# DigitalInterfaces.net
KiCad netlist of a schematic drawn in Altium Designer
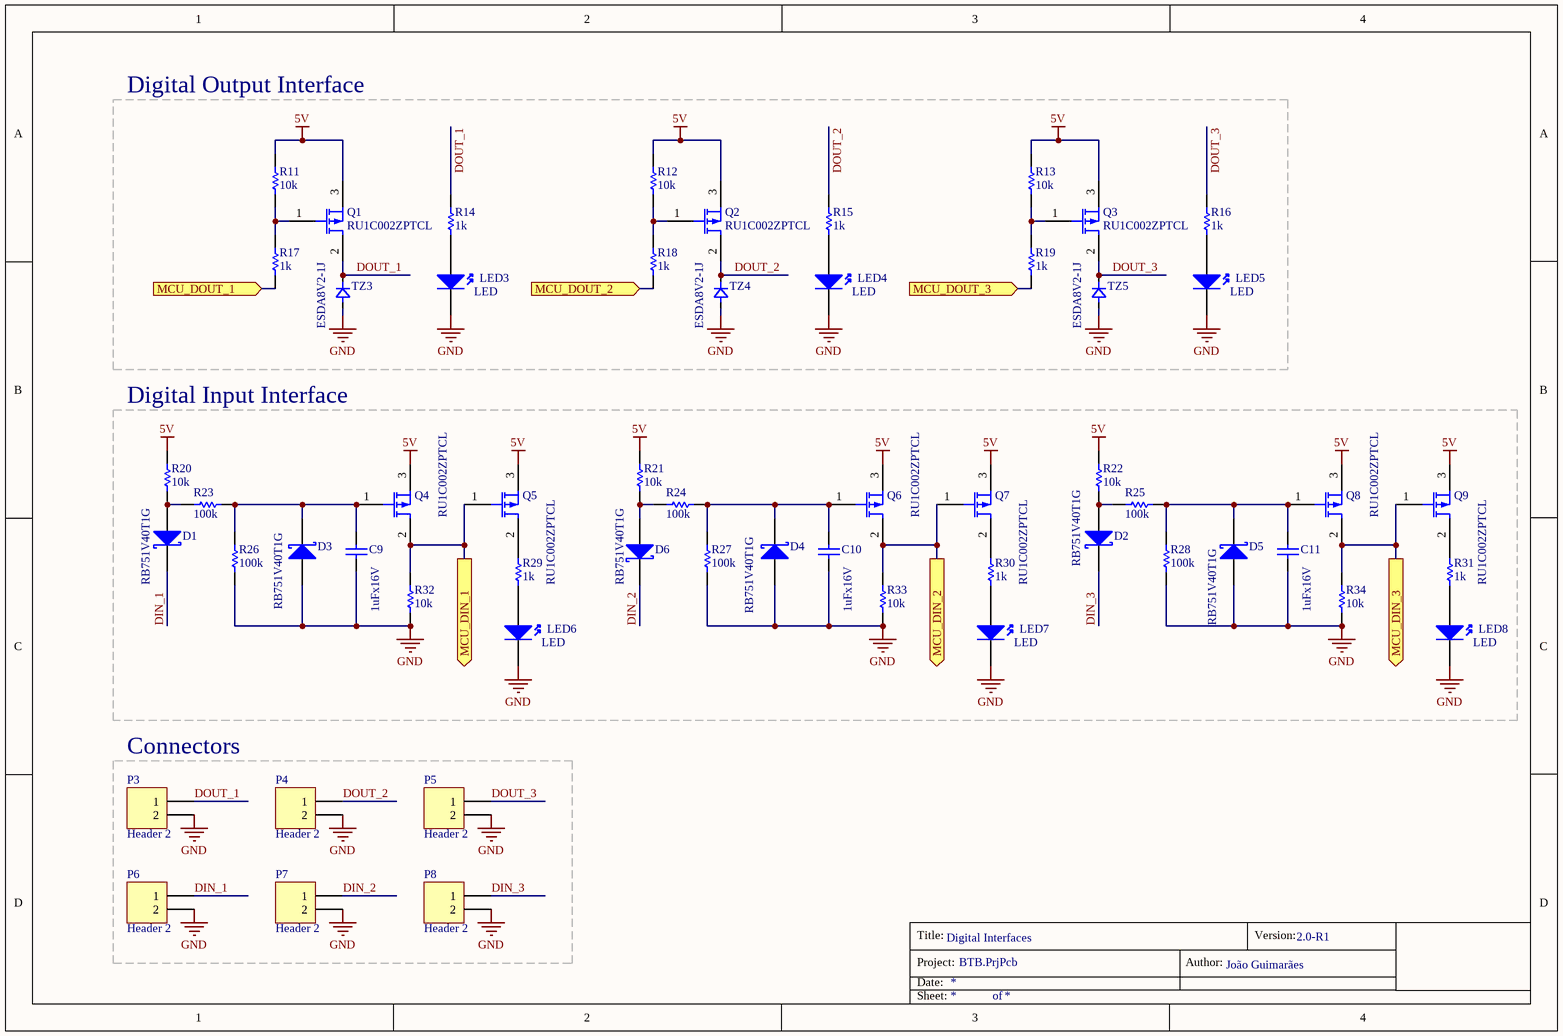
[diagram p0: DigitalInterfaces.SchDoc]

(export (version "E")
  (design (tool "Eeschema 10.0.6"))
  (components
    (comp (ref "C9")
      (value "1uFx16V")
      (footprint "DISC-0805")
      (description "Capacitor")
      (libsource (lib "IntLib") (part "Cap"))
    )
    (comp (ref "C10")
      (value "1uFx16V")
      (footprint "DISC-0805")
      (description "Capacitor")
      (libsource (lib "IntLib") (part "Cap"))
    )
    (comp (ref "C11")
      (value "1uFx16V")
      (footprint "DISC-0805")
      (description "Capacitor")
      (libsource (lib "IntLib") (part "Cap"))
    )
    (comp (ref "D1")
      (value "RB751V40T1G")
      (footprint "DISC-SOD-323")
      (description "Schottky Diode")
      (fields (field (name "PUBLISHER") "Altium Limited"))
      (libsource (lib "IntLib") (part "D Schottky"))
    )
    (comp (ref "D2")
      (value "RB751V40T1G")
      (footprint "DISC-SOD-323")
      (description "Schottky Diode")
      (fields (field (name "PUBLISHER") "Altium Limited"))
      (libsource (lib "IntLib") (part "D Schottky"))
    )
    (comp (ref "D3")
      (value "RB751V40T1G")
      (footprint "DISC-SOD-323")
      (description "Schottky Diode")
      (fields (field (name "PUBLISHER") "Altium Limited"))
      (libsource (lib "IntLib") (part "D Schottky"))
    )
    (comp (ref "D4")
      (value "RB751V40T1G")
      (footprint "DISC-SOD-323")
      (description "Schottky Diode")
      (fields (field (name "PUBLISHER") "Altium Limited"))
      (libsource (lib "IntLib") (part "D Schottky"))
    )
    (comp (ref "D5")
      (value "RB751V40T1G")
      (footprint "DISC-SOD-323")
      (description "Schottky Diode")
      (fields (field (name "PUBLISHER") "Altium Limited"))
      (libsource (lib "IntLib") (part "D Schottky"))
    )
    (comp (ref "D6")
      (value "RB751V40T1G")
      (footprint "DISC-SOD-323")
      (description "Schottky Diode")
      (fields (field (name "PUBLISHER") "Altium Limited"))
      (libsource (lib "IntLib") (part "D Schottky"))
    )
    (comp (ref "LED3") (value "LED") (footprint "DISC-LED-0.1-PTH") (libsource (lib "IntLib") (part "LED")))
    (comp (ref "LED4") (value "LED") (footprint "DISC-LED-0.1-PTH") (libsource (lib "IntLib") (part "LED")))
    (comp (ref "LED5") (value "LED") (footprint "DISC-LED-0.1-PTH") (libsource (lib "IntLib") (part "LED")))
    (comp (ref "LED6") (value "LED") (footprint "DISC-LED-0.1-PTH") (libsource (lib "IntLib") (part "LED")))
    (comp (ref "LED7") (value "LED") (footprint "DISC-LED-0.1-PTH") (libsource (lib "IntLib") (part "LED")))
    (comp (ref "LED8") (value "LED") (footprint "DISC-LED-0.1-PTH") (libsource (lib "IntLib") (part "LED")))
    (comp (ref "P3")
      (value "Header 2")
      (footprint "CON-FLEXWIRE-0.5MM2-1X2")
      (description "Header, 2-Pin")
      (fields (field (name "PUBLISHER") "Altium Limited"))
      (libsource (lib "IntLib") (part "Header 2"))
    )
    (comp (ref "P4")
      (value "Header 2")
      (footprint "CON-FLEXWIRE-0.5MM2-1X2")
      (description "Header, 2-Pin")
      (fields (field (name "PUBLISHER") "Altium Limited"))
      (libsource (lib "IntLib") (part "Header 2"))
    )
    (comp (ref "P5")
      (value "Header 2")
      (footprint "CON-FLEXWIRE-0.5MM2-1X2")
      (description "Header, 2-Pin")
      (fields (field (name "PUBLISHER") "Altium Limited"))
      (libsource (lib "IntLib") (part "Header 2"))
    )
    (comp (ref "P6")
      (value "Header 2")
      (footprint "CON-FLEXWIRE-0.5MM2-1X2")
      (description "Header, 2-Pin")
      (fields (field (name "PUBLISHER") "Altium Limited"))
      (libsource (lib "IntLib") (part "Header 2"))
    )
    (comp (ref "P7")
      (value "Header 2")
      (footprint "CON-FLEXWIRE-0.5MM2-1X2")
      (description "Header, 2-Pin")
      (fields (field (name "PUBLISHER") "Altium Limited"))
      (libsource (lib "IntLib") (part "Header 2"))
    )
    (comp (ref "P8")
      (value "Header 2")
      (footprint "CON-FLEXWIRE-0.5MM2-1X2")
      (description "Header, 2-Pin")
      (fields (field (name "PUBLISHER") "Altium Limited"))
      (libsource (lib "IntLib") (part "Header 2"))
    )
    (comp (ref "Q1")
      (value "RU1C002ZPTCL")
      (footprint "DISC-SOT-23")
      (description "P-Channel MOSFET")
      (libsource (lib "IntLib") (part "Transistor-PMOS"))
    )
    (comp (ref "Q2")
      (value "RU1C002ZPTCL")
      (footprint "DISC-SOT-23")
      (description "P-Channel MOSFET")
      (libsource (lib "IntLib") (part "Transistor-PMOS"))
    )
    (comp (ref "Q3")
      (value "RU1C002ZPTCL")
      (footprint "DISC-SOT-23")
      (description "P-Channel MOSFET")
      (libsource (lib "IntLib") (part "Transistor-PMOS"))
    )
    (comp (ref "Q4")
      (value "RU1C002ZPTCL")
      (footprint "DISC-SOT-23")
      (description "P-Channel MOSFET")
      (libsource (lib "IntLib") (part "Transistor-PMOS"))
    )
    (comp (ref "Q5")
      (value "RU1C002ZPTCL")
      (footprint "DISC-SOT-23")
      (description "P-Channel MOSFET")
      (libsource (lib "IntLib") (part "Transistor-PMOS"))
    )
    (comp (ref "Q6")
      (value "RU1C002ZPTCL")
      (footprint "DISC-SOT-23")
      (description "P-Channel MOSFET")
      (libsource (lib "IntLib") (part "Transistor-PMOS"))
    )
    (comp (ref "Q7")
      (value "RU1C002ZPTCL")
      (footprint "DISC-SOT-23")
      (description "P-Channel MOSFET")
      (libsource (lib "IntLib") (part "Transistor-PMOS"))
    )
    (comp (ref "Q8")
      (value "RU1C002ZPTCL")
      (footprint "DISC-SOT-23")
      (description "P-Channel MOSFET")
      (libsource (lib "IntLib") (part "Transistor-PMOS"))
    )
    (comp (ref "Q9")
      (value "RU1C002ZPTCL")
      (footprint "DISC-SOT-23")
      (description "P-Channel MOSFET")
      (libsource (lib "IntLib") (part "Transistor-PMOS"))
    )
    (comp (ref "R11")
      (value "10k")
      (footprint "DISC-0805")
      (description "Resistor")
      (libsource (lib "IntLib") (part "Res"))
    )
    (comp (ref "R12")
      (value "10k")
      (footprint "DISC-0805")
      (description "Resistor")
      (libsource (lib "IntLib") (part "Res"))
    )
    (comp (ref "R13")
      (value "10k")
      (footprint "DISC-0805")
      (description "Resistor")
      (libsource (lib "IntLib") (part "Res"))
    )
    (comp (ref "R14")
      (value "1k")
      (footprint "DISC-0805")
      (description "Resistor")
      (libsource (lib "IntLib") (part "Res"))
    )
    (comp (ref "R15")
      (value "1k")
      (footprint "DISC-0805")
      (description "Resistor")
      (libsource (lib "IntLib") (part "Res"))
    )
    (comp (ref "R16")
      (value "1k")
      (footprint "DISC-0805")
      (description "Resistor")
      (libsource (lib "IntLib") (part "Res"))
    )
    (comp (ref "R17")
      (value "1k")
      (footprint "DISC-0805")
      (description "Resistor")
      (libsource (lib "IntLib") (part "Res"))
    )
    (comp (ref "R18")
      (value "1k")
      (footprint "DISC-0805")
      (description "Resistor")
      (libsource (lib "IntLib") (part "Res"))
    )
    (comp (ref "R19")
      (value "1k")
      (footprint "DISC-0805")
      (description "Resistor")
      (libsource (lib "IntLib") (part "Res"))
    )
    (comp (ref "R20")
      (value "10k")
      (footprint "DISC-0805")
      (description "Resistor")
      (libsource (lib "IntLib") (part "Res"))
    )
    (comp (ref "R21")
      (value "10k")
      (footprint "DISC-0805")
      (description "Resistor")
      (libsource (lib "IntLib") (part "Res"))
    )
    (comp (ref "R22")
      (value "10k")
      (footprint "DISC-0805")
      (description "Resistor")
      (libsource (lib "IntLib") (part "Res"))
    )
    (comp (ref "R23")
      (value "100k")
      (footprint "DISC-0805")
      (description "Resistor")
      (libsource (lib "IntLib") (part "Res"))
    )
    (comp (ref "R24")
      (value "100k")
      (footprint "DISC-0805")
      (description "Resistor")
      (libsource (lib "IntLib") (part "Res"))
    )
    (comp (ref "R25")
      (value "100k")
      (footprint "DISC-0805")
      (description "Resistor")
      (libsource (lib "IntLib") (part "Res"))
    )
    (comp (ref "R26")
      (value "100k")
      (footprint "DISC-0805")
      (description "Resistor")
      (libsource (lib "IntLib") (part "Res"))
    )
    (comp (ref "R27")
      (value "100k")
      (footprint "DISC-0805")
      (description "Resistor")
      (libsource (lib "IntLib") (part "Res"))
    )
    (comp (ref "R28")
      (value "100k")
      (footprint "DISC-0805")
      (description "Resistor")
      (libsource (lib "IntLib") (part "Res"))
    )
    (comp (ref "R29")
      (value "1k")
      (footprint "DISC-0805")
      (description "Resistor")
      (libsource (lib "IntLib") (part "Res"))
    )
    (comp (ref "R30")
      (value "1k")
      (footprint "DISC-0805")
      (description "Resistor")
      (libsource (lib "IntLib") (part "Res"))
    )
    (comp (ref "R31")
      (value "1k")
      (footprint "DISC-0805")
      (description "Resistor")
      (libsource (lib "IntLib") (part "Res"))
    )
    (comp (ref "R32")
      (value "10k")
      (footprint "DISC-0805")
      (description "Resistor")
      (libsource (lib "IntLib") (part "Res"))
    )
    (comp (ref "R33")
      (value "10k")
      (footprint "DISC-0805")
      (description "Resistor")
      (libsource (lib "IntLib") (part "Res"))
    )
    (comp (ref "R34")
      (value "10k")
      (footprint "DISC-0805")
      (description "Resistor")
      (libsource (lib "IntLib") (part "Res"))
    )
    (comp (ref "TZ3")
      (value "ESDA8V2-1J")
      (footprint "DISC-SOD-323")
      (description "TVZ-Unidirectional")
      (libsource (lib "IntLib") (part "TVZ-Unidirectional"))
    )
    (comp (ref "TZ4")
      (value "ESDA8V2-1J")
      (footprint "DISC-SOD-323")
      (description "TVZ-Unidirectional")
      (libsource (lib "IntLib") (part "TVZ-Unidirectional"))
    )
    (comp (ref "TZ5")
      (value "ESDA8V2-1J")
      (footprint "DISC-SOD-323")
      (description "TVZ-Unidirectional")
      (libsource (lib "IntLib") (part "TVZ-Unidirectional"))
    )
  )
  (nets
    (net (code "1") (name "/DIN_1") (class "Default")
      (node (ref "D1") (pin "2") (pinfunction "K_2") (pintype "passive"))
      (node (ref "P6") (pin "1") (pinfunction "1_1") (pintype "passive"))
    )
    (net (code "2") (name "/DIN_2") (class "Default")
      (node (ref "D6") (pin "2") (pinfunction "K_2") (pintype "passive"))
      (node (ref "P7") (pin "1") (pinfunction "1_1") (pintype "passive"))
    )
    (net (code "3") (name "/DIN_3") (class "Default")
      (node (ref "D2") (pin "2") (pinfunction "K_2") (pintype "passive"))
      (node (ref "P8") (pin "1") (pinfunction "1_1") (pintype "passive"))
    )
    (net (code "4") (name "/DOUT_1") (class "Default")
      (node (ref "P3") (pin "1") (pinfunction "1_1") (pintype "passive"))
      (node (ref "Q1") (pin "2") (pinfunction "D_2") (pintype "passive"))
      (node (ref "R14") (pin "2") (pinfunction "2_2") (pintype "passive"))
      (node (ref "TZ3") (pin "2") (pinfunction "C_2") (pintype "passive"))
    )
    (net (code "5") (name "/DOUT_2") (class "Default")
      (node (ref "P4") (pin "1") (pinfunction "1_1") (pintype "passive"))
      (node (ref "Q2") (pin "2") (pinfunction "D_2") (pintype "passive"))
      (node (ref "R15") (pin "2") (pinfunction "2_2") (pintype "passive"))
      (node (ref "TZ4") (pin "2") (pinfunction "C_2") (pintype "passive"))
    )
    (net (code "6") (name "/DOUT_3") (class "Default")
      (node (ref "P5") (pin "1") (pinfunction "1_1") (pintype "passive"))
      (node (ref "Q3") (pin "2") (pinfunction "D_2") (pintype "passive"))
      (node (ref "R16") (pin "2") (pinfunction "2_2") (pintype "passive"))
      (node (ref "TZ5") (pin "2") (pinfunction "C_2") (pintype "passive"))
    )
    (net (code "7") (name "/MCU_DIN_1") (class "Default")
      (node (ref "Q4") (pin "2") (pinfunction "D_2") (pintype "passive"))
      (node (ref "Q5") (pin "1") (pinfunction "G_1") (pintype "passive"))
      (node (ref "R32") (pin "2") (pinfunction "2_2") (pintype "passive"))
    )
    (net (code "8") (name "/MCU_DIN_2") (class "Default")
      (node (ref "Q6") (pin "2") (pinfunction "D_2") (pintype "passive"))
      (node (ref "Q7") (pin "1") (pinfunction "G_1") (pintype "passive"))
      (node (ref "R33") (pin "2") (pinfunction "2_2") (pintype "passive"))
    )
    (net (code "9") (name "/MCU_DIN_3") (class "Default")
      (node (ref "Q8") (pin "2") (pinfunction "D_2") (pintype "passive"))
      (node (ref "Q9") (pin "1") (pinfunction "G_1") (pintype "passive"))
      (node (ref "R34") (pin "2") (pinfunction "2_2") (pintype "passive"))
    )
    (net (code "10") (name "/MCU_DOUT_1") (class "Default")
      (node (ref "R17") (pin "2") (pinfunction "2_2") (pintype "passive"))
    )
    (net (code "11") (name "/MCU_DOUT_2") (class "Default")
      (node (ref "R18") (pin "2") (pinfunction "2_2") (pintype "passive"))
    )
    (net (code "12") (name "/MCU_DOUT_3") (class "Default")
      (node (ref "R19") (pin "2") (pinfunction "2_2") (pintype "passive"))
    )
    (net (code "13") (name "5V") (class "Default")
      (node (ref "Q1") (pin "3") (pinfunction "S_3") (pintype "passive"))
      (node (ref "Q2") (pin "3") (pinfunction "S_3") (pintype "passive"))
      (node (ref "Q3") (pin "3") (pinfunction "S_3") (pintype "passive"))
      (node (ref "Q4") (pin "3") (pinfunction "S_3") (pintype "passive"))
      (node (ref "Q5") (pin "3") (pinfunction "S_3") (pintype "passive"))
      (node (ref "Q6") (pin "3") (pinfunction "S_3") (pintype "passive"))
      (node (ref "Q7") (pin "3") (pinfunction "S_3") (pintype "passive"))
      (node (ref "Q8") (pin "3") (pinfunction "S_3") (pintype "passive"))
      (node (ref "Q9") (pin "3") (pinfunction "S_3") (pintype "passive"))
      (node (ref "R11") (pin "1") (pinfunction "1_1") (pintype "passive"))
      (node (ref "R12") (pin "1") (pinfunction "1_1") (pintype "passive"))
      (node (ref "R13") (pin "1") (pinfunction "1_1") (pintype "passive"))
      (node (ref "R20") (pin "1") (pinfunction "1_1") (pintype "passive"))
      (node (ref "R21") (pin "1") (pinfunction "1_1") (pintype "passive"))
      (node (ref "R22") (pin "1") (pinfunction "1_1") (pintype "passive"))
    )
    (net (code "14") (name "GND") (class "Default")
      (node (ref "C10") (pin "1") (pinfunction "1_1") (pintype "passive"))
      (node (ref "C11") (pin "1") (pinfunction "1_1") (pintype "passive"))
      (node (ref "C9") (pin "1") (pinfunction "1_1") (pintype "passive"))
      (node (ref "D3") (pin "1") (pinfunction "A_1") (pintype "passive"))
      (node (ref "D4") (pin "1") (pinfunction "A_1") (pintype "passive"))
      (node (ref "D5") (pin "1") (pinfunction "A_1") (pintype "passive"))
      (node (ref "LED3") (pin "2") (pinfunction "K_2") (pintype "passive"))
      (node (ref "LED4") (pin "2") (pinfunction "K_2") (pintype "passive"))
      (node (ref "LED5") (pin "2") (pinfunction "K_2") (pintype "passive"))
      (node (ref "LED6") (pin "2") (pinfunction "K_2") (pintype "passive"))
      (node (ref "LED7") (pin "2") (pinfunction "K_2") (pintype "passive"))
      (node (ref "LED8") (pin "2") (pinfunction "K_2") (pintype "passive"))
      (node (ref "P3") (pin "2") (pinfunction "2_2") (pintype "passive"))
      (node (ref "P4") (pin "2") (pinfunction "2_2") (pintype "passive"))
      (node (ref "P5") (pin "2") (pinfunction "2_2") (pintype "passive"))
      (node (ref "P6") (pin "2") (pinfunction "2_2") (pintype "passive"))
      (node (ref "P7") (pin "2") (pinfunction "2_2") (pintype "passive"))
      (node (ref "P8") (pin "2") (pinfunction "2_2") (pintype "passive"))
      (node (ref "R26") (pin "1") (pinfunction "1_1") (pintype "passive"))
      (node (ref "R27") (pin "1") (pinfunction "1_1") (pintype "passive"))
      (node (ref "R28") (pin "1") (pinfunction "1_1") (pintype "passive"))
      (node (ref "R32") (pin "1") (pinfunction "1_1") (pintype "passive"))
      (node (ref "R33") (pin "1") (pinfunction "1_1") (pintype "passive"))
      (node (ref "R34") (pin "1") (pinfunction "1_1") (pintype "passive"))
      (node (ref "TZ3") (pin "1") (pinfunction "A_1") (pintype "passive"))
      (node (ref "TZ4") (pin "1") (pinfunction "A_1") (pintype "passive"))
      (node (ref "TZ5") (pin "1") (pinfunction "A_1") (pintype "passive"))
    )
    (net (code "15") (name "Net-(D1-A)") (class "Default")
      (node (ref "D1") (pin "1") (pinfunction "A_1") (pintype "passive"))
      (node (ref "R20") (pin "2") (pinfunction "2_2") (pintype "passive"))
      (node (ref "R23") (pin "2") (pinfunction "2_2") (pintype "passive"))
    )
    (net (code "16") (name "Net-(D2-A)") (class "Default")
      (node (ref "D2") (pin "1") (pinfunction "A_1") (pintype "passive"))
      (node (ref "R22") (pin "2") (pinfunction "2_2") (pintype "passive"))
      (node (ref "R25") (pin "1") (pinfunction "1_1") (pintype "passive"))
    )
    (net (code "17") (name "Net-(D3-K)") (class "Default")
      (node (ref "C9") (pin "2") (pinfunction "2_2") (pintype "passive"))
      (node (ref "D3") (pin "2") (pinfunction "K_2") (pintype "passive"))
      (node (ref "Q4") (pin "1") (pinfunction "G_1") (pintype "passive"))
      (node (ref "R23") (pin "1") (pinfunction "1_1") (pintype "passive"))
      (node (ref "R26") (pin "2") (pinfunction "2_2") (pintype "passive"))
    )
    (net (code "18") (name "Net-(D4-K)") (class "Default")
      (node (ref "C10") (pin "2") (pinfunction "2_2") (pintype "passive"))
      (node (ref "D4") (pin "2") (pinfunction "K_2") (pintype "passive"))
      (node (ref "Q6") (pin "1") (pinfunction "G_1") (pintype "passive"))
      (node (ref "R24") (pin "2") (pinfunction "2_2") (pintype "passive"))
      (node (ref "R27") (pin "2") (pinfunction "2_2") (pintype "passive"))
    )
    (net (code "19") (name "Net-(D5-K)") (class "Default")
      (node (ref "C11") (pin "2") (pinfunction "2_2") (pintype "passive"))
      (node (ref "D5") (pin "2") (pinfunction "K_2") (pintype "passive"))
      (node (ref "Q8") (pin "1") (pinfunction "G_1") (pintype "passive"))
      (node (ref "R25") (pin "2") (pinfunction "2_2") (pintype "passive"))
      (node (ref "R28") (pin "2") (pinfunction "2_2") (pintype "passive"))
    )
    (net (code "20") (name "Net-(D6-A)") (class "Default")
      (node (ref "D6") (pin "1") (pinfunction "A_1") (pintype "passive"))
      (node (ref "R21") (pin "2") (pinfunction "2_2") (pintype "passive"))
      (node (ref "R24") (pin "1") (pinfunction "1_1") (pintype "passive"))
    )
    (net (code "21") (name "Net-(LED3-A)") (class "Default")
      (node (ref "LED3") (pin "1") (pinfunction "A_1") (pintype "passive"))
      (node (ref "R14") (pin "1") (pinfunction "1_1") (pintype "passive"))
    )
    (net (code "22") (name "Net-(LED4-A)") (class "Default")
      (node (ref "LED4") (pin "1") (pinfunction "A_1") (pintype "passive"))
      (node (ref "R15") (pin "1") (pinfunction "1_1") (pintype "passive"))
    )
    (net (code "23") (name "Net-(LED5-A)") (class "Default")
      (node (ref "LED5") (pin "1") (pinfunction "A_1") (pintype "passive"))
      (node (ref "R16") (pin "1") (pinfunction "1_1") (pintype "passive"))
    )
    (net (code "24") (name "Net-(LED6-A)") (class "Default")
      (node (ref "LED6") (pin "1") (pinfunction "A_1") (pintype "passive"))
      (node (ref "R29") (pin "1") (pinfunction "1_1") (pintype "passive"))
    )
    (net (code "25") (name "Net-(LED7-A)") (class "Default")
      (node (ref "LED7") (pin "1") (pinfunction "A_1") (pintype "passive"))
      (node (ref "R30") (pin "1") (pinfunction "1_1") (pintype "passive"))
    )
    (net (code "26") (name "Net-(LED8-A)") (class "Default")
      (node (ref "LED8") (pin "1") (pinfunction "A_1") (pintype "passive"))
      (node (ref "R31") (pin "1") (pinfunction "1_1") (pintype "passive"))
    )
    (net (code "27") (name "Net-(Q1-G)") (class "Default")
      (node (ref "Q1") (pin "1") (pinfunction "G_1") (pintype "passive"))
      (node (ref "R11") (pin "2") (pinfunction "2_2") (pintype "passive"))
      (node (ref "R17") (pin "1") (pinfunction "1_1") (pintype "passive"))
    )
    (net (code "28") (name "Net-(Q2-G)") (class "Default")
      (node (ref "Q2") (pin "1") (pinfunction "G_1") (pintype "passive"))
      (node (ref "R12") (pin "2") (pinfunction "2_2") (pintype "passive"))
      (node (ref "R18") (pin "1") (pinfunction "1_1") (pintype "passive"))
    )
    (net (code "29") (name "Net-(Q3-G)") (class "Default")
      (node (ref "Q3") (pin "1") (pinfunction "G_1") (pintype "passive"))
      (node (ref "R13") (pin "2") (pinfunction "2_2") (pintype "passive"))
      (node (ref "R19") (pin "1") (pinfunction "1_1") (pintype "passive"))
    )
    (net (code "30") (name "Net-(Q5-D)") (class "Default")
      (node (ref "Q5") (pin "2") (pinfunction "D_2") (pintype "passive"))
      (node (ref "R29") (pin "2") (pinfunction "2_2") (pintype "passive"))
    )
    (net (code "31") (name "Net-(Q7-D)") (class "Default")
      (node (ref "Q7") (pin "2") (pinfunction "D_2") (pintype "passive"))
      (node (ref "R30") (pin "2") (pinfunction "2_2") (pintype "passive"))
    )
    (net (code "32") (name "Net-(Q9-D)") (class "Default")
      (node (ref "Q9") (pin "2") (pinfunction "D_2") (pintype "passive"))
      (node (ref "R31") (pin "2") (pinfunction "2_2") (pintype "passive"))
    )
  )
)
